# LL1540_tr.net
KiCad netlist of a schematic drawn in EAGLE
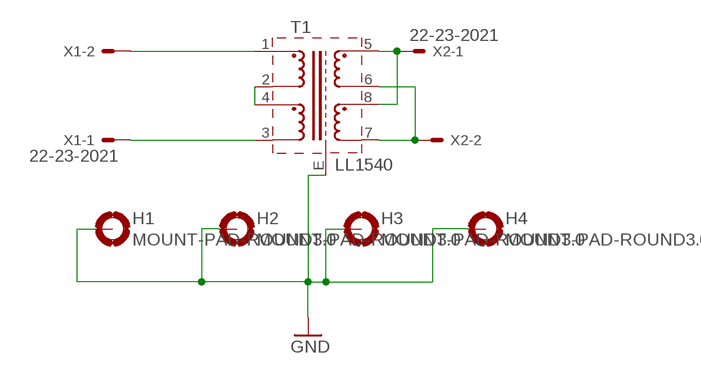
[diagram p0: schematic, sheet 1]

(export (version "E")
  (design (tool "Eeschema 10.0.6"))
  (components
    (comp (ref "H1")
      (value "MOUNT-PAD-ROUND3.0")
      (footprint "eagle-import:3,0-PAD")
      (libsource (lib "eagle-import") (part "MOUNT-PAD-ROUND3.0"))
    )
    (comp (ref "H2")
      (value "MOUNT-PAD-ROUND3.0")
      (footprint "eagle-import:3,0-PAD")
      (libsource (lib "eagle-import") (part "MOUNT-PAD-ROUND3.0"))
    )
    (comp (ref "H3")
      (value "MOUNT-PAD-ROUND3.0")
      (footprint "eagle-import:3,0-PAD")
      (libsource (lib "eagle-import") (part "MOUNT-PAD-ROUND3.0"))
    )
    (comp (ref "H4")
      (value "MOUNT-PAD-ROUND3.0")
      (footprint "eagle-import:3,0-PAD")
      (libsource (lib "eagle-import") (part "MOUNT-PAD-ROUND3.0"))
    )
    (comp (ref "T1")
      (value "LL1540")
      (footprint "eagle-import:LL1540")
      (libsource (lib "eagle-import") (part "LL1540"))
    )
    (comp (ref "X1")
      (value "22-23-2021")
      (footprint "eagle-import:22-23-2021")
      (fields (field (name "MF") "MOLEX"))
      (libsource (lib "eagle-import") (part "22-23-2021"))
    )
    (comp (ref "X2")
      (value "22-23-2021")
      (footprint "eagle-import:22-23-2021")
      (fields (field (name "MF") "MOLEX"))
      (libsource (lib "eagle-import") (part "22-23-2021"))
    )
  )
  (nets
    (net (code "1") (name "GND") (class "Default")
      (node (ref "H1") (pin "B3,0") (pinfunction "MOUNT_B3,0") (pintype "passive"))
      (node (ref "H2") (pin "B3,0") (pinfunction "MOUNT_B3,0") (pintype "passive"))
      (node (ref "H3") (pin "B3,0") (pinfunction "MOUNT_B3,0") (pintype "passive"))
      (node (ref "H4") (pin "B3,0") (pinfunction "MOUNT_B3,0") (pintype "passive"))
      (node (ref "T1") (pin "E") (pinfunction "E_E") (pintype "passive"))
    )
    (net (code "2") (name "Net-(T1-Pad2)") (class "Default")
      (node (ref "T1") (pin "2") (pinfunction "2_2") (pintype "passive"))
      (node (ref "T1") (pin "4") (pinfunction "4_4") (pintype "passive"))
    )
    (net (code "3") (name "Net-(X1A-S)") (class "Default")
      (node (ref "T1") (pin "3") (pinfunction "3_3") (pintype "passive"))
      (node (ref "X1") (pin "1") (pinfunction "S_1") (pintype "passive"))
    )
    (net (code "4") (name "Net-(X1B-S)") (class "Default")
      (node (ref "T1") (pin "1") (pinfunction "1_1") (pintype "passive"))
      (node (ref "X1") (pin "2") (pinfunction "S_2") (pintype "passive"))
    )
    (net (code "5") (name "Net-(X2A-S)") (class "Default")
      (node (ref "T1") (pin "5") (pinfunction "5_5") (pintype "passive"))
      (node (ref "T1") (pin "8") (pinfunction "8_8") (pintype "passive"))
      (node (ref "X2") (pin "1") (pinfunction "S_1") (pintype "passive"))
    )
    (net (code "6") (name "Net-(X2B-S)") (class "Default")
      (node (ref "T1") (pin "6") (pinfunction "6_6") (pintype "passive"))
      (node (ref "T1") (pin "7") (pinfunction "7_7") (pintype "passive"))
      (node (ref "X2") (pin "2") (pinfunction "S_2") (pintype "passive"))
    )
  )
)
